# STorM32_Micro_Logger_v132_micro.net
KiCad netlist of a schematic drawn in EAGLE
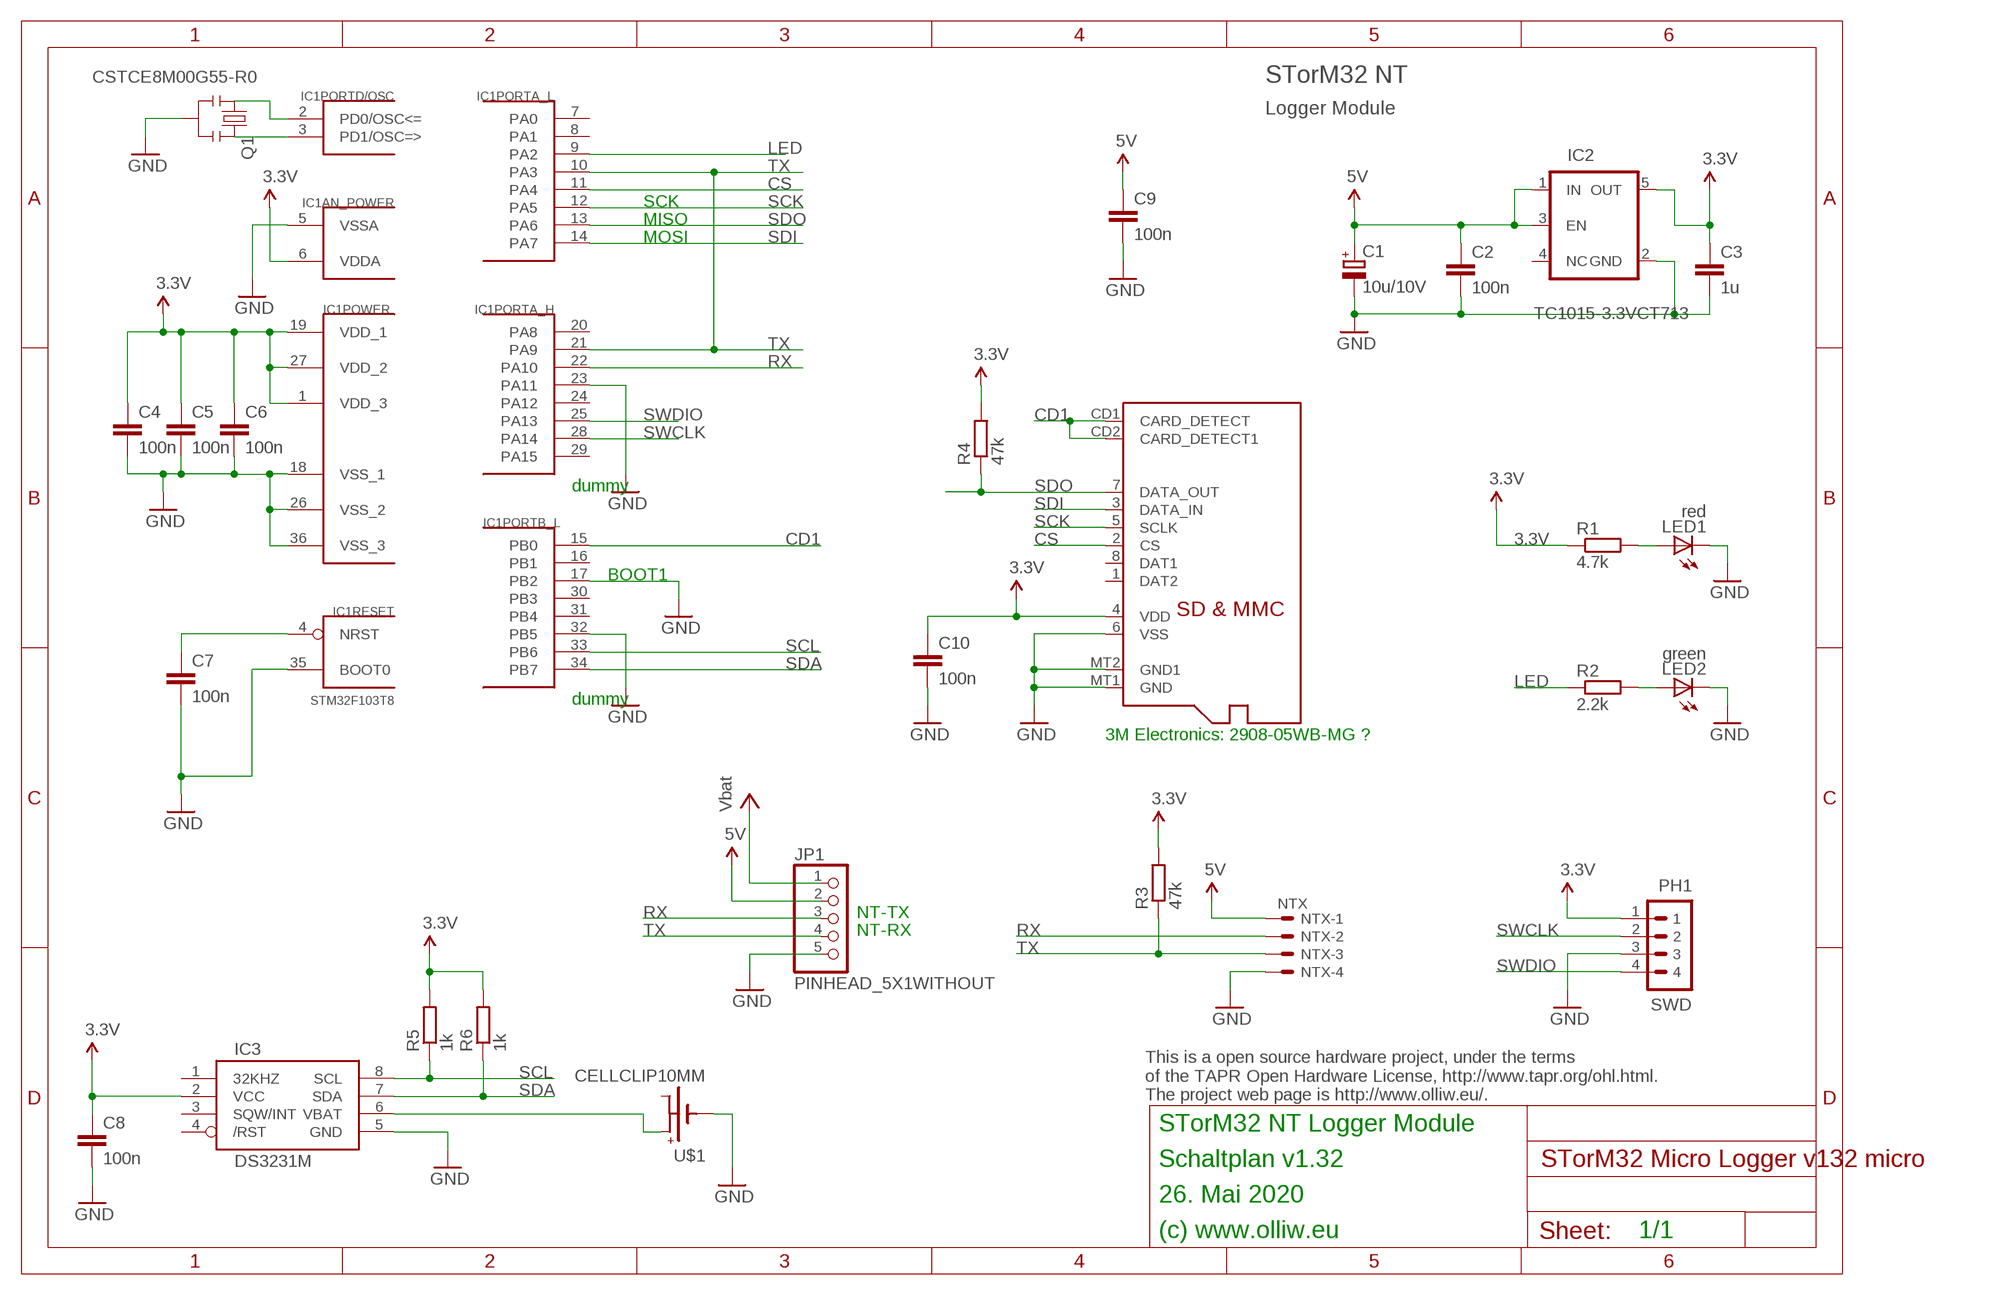
[diagram p0: schematic, sheet 1]

(export (version "E")
  (design (tool "Eeschema 10.0.6"))
  (components
    (comp (ref "C1")
      (value "10u/10V")
      (footprint "eagle-import:SMC_B")
      (libsource (lib "eagle-import") (part "CPOL-EUSMCB"))
    )
    (comp (ref "C2")
      (value "100n")
      (footprint "eagle-import:C0603")
      (libsource (lib "eagle-import") (part "C-EUC0603"))
    )
    (comp (ref "C3")
      (value "1u")
      (footprint "eagle-import:C0603")
      (libsource (lib "eagle-import") (part "C-EUC0603"))
    )
    (comp (ref "C4")
      (value "100n")
      (footprint "eagle-import:C0402")
      (libsource (lib "eagle-import") (part "C-EUC0402"))
    )
    (comp (ref "C5")
      (value "100n")
      (footprint "eagle-import:C0402")
      (libsource (lib "eagle-import") (part "C-EUC0402"))
    )
    (comp (ref "C6")
      (value "100n")
      (footprint "eagle-import:C0402")
      (libsource (lib "eagle-import") (part "C-EUC0402"))
    )
    (comp (ref "C7")
      (value "100n")
      (footprint "eagle-import:C0402")
      (libsource (lib "eagle-import") (part "C-EUC0402"))
    )
    (comp (ref "C8")
      (value "100n")
      (footprint "eagle-import:C0402")
      (libsource (lib "eagle-import") (part "C-EUC0402"))
    )
    (comp (ref "C9")
      (value "100n")
      (footprint "eagle-import:C0603")
      (libsource (lib "eagle-import") (part "C-EUC0603"))
    )
    (comp (ref "C10")
      (value "100n")
      (footprint "eagle-import:C0402")
      (libsource (lib "eagle-import") (part "C-EUC0402"))
    )
    (comp (ref "IC1")
      (value "STM32F103T8")
      (footprint "eagle-import:VFQFPN36")
      (libsource (lib "eagle-import") (part "STM32F10XTXU6"))
    )
    (comp (ref "IC2")
      (value "TC1015-3.3VCT713")
      (footprint "eagle-import:SOT23-5")
      (libsource (lib "eagle-import") (part "V_REG_TPS76433SOT23-5"))
    )
    (comp (ref "IC3")
      (value "DS3231M")
      (footprint "eagle-import:SO08")
      (libsource (lib "eagle-import") (part "DS3231M"))
    )
    (comp (ref "JP1")
      (value "PINHEAD_5X1WITHOUT")
      (footprint "eagle-import:PINHEAD_5X1_WO")
      (libsource (lib "eagle-import") (part "PINHEAD_5X1WITHOUT"))
    )
    (comp (ref "LED1")
      (value "red")
      (footprint "eagle-import:CHIPLED_0603")
      (libsource (lib "eagle-import") (part "LEDCHIPLED_0603"))
    )
    (comp (ref "LED2")
      (value "green")
      (footprint "eagle-import:CHIPLED_0603")
      (libsource (lib "eagle-import") (part "LEDCHIPLED_0603"))
    )
    (comp (ref "NTX")
      (value "NTX")
      (footprint "eagle-import:SM04B-SRSS-TB")
      (libsource (lib "eagle-import") (part "?M04B-SRSS-TBS"))
    )
    (comp (ref "PH1")
      (value "SWD")
      (footprint "eagle-import:4X1_1P27_OCT_BILEX")
      (libsource (lib "eagle-import") (part "P4X1_1P27-OCT_BILEX"))
    )
    (comp (ref "Q1")
      (value "CSTCE8M00G55-R0")
      (footprint "eagle-import:RESONATOR-SMD")
      (libsource (lib "eagle-import") (part "RESONATORSMD"))
    )
    (comp (ref "R1")
      (value "4.7k")
      (footprint "eagle-import:R0402")
      (libsource (lib "eagle-import") (part "R-EU_R0402"))
    )
    (comp (ref "R2")
      (value "2.2k")
      (footprint "eagle-import:R0402")
      (libsource (lib "eagle-import") (part "R-EU_R0402"))
    )
    (comp (ref "R3")
      (value "47k")
      (footprint "eagle-import:R0402")
      (libsource (lib "eagle-import") (part "R-EU_R0402"))
    )
    (comp (ref "R4")
      (value "47k")
      (footprint "eagle-import:R0402")
      (libsource (lib "eagle-import") (part "R-EU_R0402"))
    )
    (comp (ref "R5")
      (value "1k")
      (footprint "eagle-import:R0402")
      (libsource (lib "eagle-import") (part "R-EU_R0402"))
    )
    (comp (ref "R6")
      (value "1k")
      (footprint "eagle-import:R0402")
      (libsource (lib "eagle-import") (part "R-EU_R0402"))
    )
    (comp (ref "U$1")
      (value "CELLCLIP10MM")
      (footprint "eagle-import:CELLCLIP-10MM")
      (libsource (lib "eagle-import") (part "CELLCLIP10MM"))
    )
    (comp (ref "U1")
      (value "3M 2908-05WB-MG ??")
      (footprint "eagle-import:MICROSD")
      (libsource (lib "eagle-import") (part "MICROSD"))
    )
  )
  (nets
    (net (code "1") (name "/CD1") (class "Default")
      (node (ref "IC1") (pin "15") (pinfunction "PB0_15") (pintype "bidirectional"))
      (node (ref "U1") (pin "CD1") (pinfunction "CARD_DETECT_CD1") (pintype "passive"))
      (node (ref "U1") (pin "CD2") (pinfunction "CARD_DETECT1_CD2") (pintype "passive"))
    )
    (net (code "2") (name "/CS") (class "Default")
      (node (ref "IC1") (pin "11") (pinfunction "PA4_11") (pintype "bidirectional"))
      (node (ref "U1") (pin "2") (pinfunction "CS_2") (pintype "input"))
    )
    (net (code "3") (name "/LED") (class "Default")
      (node (ref "IC1") (pin "9") (pinfunction "PA2_9") (pintype "bidirectional"))
      (node (ref "R2") (pin "1") (pinfunction "1_1") (pintype "passive"))
    )
    (net (code "4") (name "/RX") (class "Default")
      (node (ref "IC1") (pin "22") (pinfunction "PA10_22") (pintype "bidirectional"))
      (node (ref "JP1") (pin "3") (pinfunction "3_3") (pintype "passive"))
      (node (ref "NTX") (pin "2") (pinfunction "S_2") (pintype "passive"))
    )
    (net (code "5") (name "/SCK") (class "Default")
      (node (ref "IC1") (pin "12") (pinfunction "PA5_12") (pintype "bidirectional"))
      (node (ref "U1") (pin "5") (pinfunction "SCLK_5") (pintype "input"))
    )
    (net (code "6") (name "/SCL") (class "Default")
      (node (ref "IC1") (pin "33") (pinfunction "PB6_33") (pintype "bidirectional"))
      (node (ref "IC3") (pin "8") (pinfunction "SCL_8") (pintype "bidirectional"))
      (node (ref "R5") (pin "1") (pinfunction "1_1") (pintype "passive"))
    )
    (net (code "7") (name "/SDA") (class "Default")
      (node (ref "IC1") (pin "34") (pinfunction "PB7_34") (pintype "bidirectional"))
      (node (ref "IC3") (pin "7") (pinfunction "SDA_7") (pintype "bidirectional"))
      (node (ref "R6") (pin "1") (pinfunction "1_1") (pintype "passive"))
    )
    (net (code "8") (name "/SDI") (class "Default")
      (node (ref "IC1") (pin "14") (pinfunction "PA7_14") (pintype "bidirectional"))
      (node (ref "U1") (pin "3") (pinfunction "DATA_IN_3") (pintype "input"))
    )
    (net (code "9") (name "/SDO") (class "Default")
      (node (ref "IC1") (pin "13") (pinfunction "PA6_13") (pintype "bidirectional"))
      (node (ref "R4") (pin "1") (pinfunction "1_1") (pintype "passive"))
      (node (ref "U1") (pin "7") (pinfunction "DATA_OUT_7") (pintype "output"))
    )
    (net (code "10") (name "/SWCLK") (class "Default")
      (node (ref "IC1") (pin "28") (pinfunction "PA14_28") (pintype "bidirectional"))
      (node (ref "PH1") (pin "2") (pinfunction "2_2") (pintype "passive"))
    )
    (net (code "11") (name "/SWDIO") (class "Default")
      (node (ref "IC1") (pin "25") (pinfunction "PA13_25") (pintype "bidirectional"))
      (node (ref "PH1") (pin "4") (pinfunction "4_4") (pintype "passive"))
    )
    (net (code "12") (name "/TX") (class "Default")
      (node (ref "IC1") (pin "10") (pinfunction "PA3_10") (pintype "bidirectional"))
      (node (ref "IC1") (pin "21") (pinfunction "PA9_21") (pintype "bidirectional"))
      (node (ref "JP1") (pin "4") (pinfunction "4_4") (pintype "passive"))
      (node (ref "NTX") (pin "3") (pinfunction "S_3") (pintype "passive"))
      (node (ref "R3") (pin "1") (pinfunction "1_1") (pintype "passive"))
    )
    (net (code "13") (name "3.3V") (class "Default")
      (node (ref "C10") (pin "1") (pinfunction "1_1") (pintype "passive"))
      (node (ref "C3") (pin "1") (pinfunction "1_1") (pintype "passive"))
      (node (ref "C4") (pin "1") (pinfunction "1_1") (pintype "passive"))
      (node (ref "C5") (pin "1") (pinfunction "1_1") (pintype "passive"))
      (node (ref "C6") (pin "1") (pinfunction "1_1") (pintype "passive"))
      (node (ref "C8") (pin "1") (pinfunction "1_1") (pintype "passive"))
      (node (ref "IC1") (pin "1") (pinfunction "VDD_3_1") (pintype "power_in"))
      (node (ref "IC1") (pin "19") (pinfunction "VDD_1_19") (pintype "power_in"))
      (node (ref "IC1") (pin "27") (pinfunction "VDD_2_27") (pintype "power_in"))
      (node (ref "IC1") (pin "6") (pinfunction "VDDA_6") (pintype "power_in"))
      (node (ref "IC2") (pin "5") (pinfunction "OUT_5") (pintype "output"))
      (node (ref "IC3") (pin "2") (pinfunction "VCC_2") (pintype "power_in"))
      (node (ref "PH1") (pin "1") (pinfunction "1_1") (pintype "passive"))
      (node (ref "R1") (pin "1") (pinfunction "1_1") (pintype "passive"))
      (node (ref "R3") (pin "2") (pinfunction "2_2") (pintype "passive"))
      (node (ref "R4") (pin "2") (pinfunction "2_2") (pintype "passive"))
      (node (ref "R5") (pin "2") (pinfunction "2_2") (pintype "passive"))
      (node (ref "R6") (pin "2") (pinfunction "2_2") (pintype "passive"))
      (node (ref "U1") (pin "4") (pinfunction "VDD_4") (pintype "power_in"))
    )
    (net (code "14") (name "5V") (class "Default")
      (node (ref "C1") (pin "+") (pinfunction "+_+") (pintype "passive"))
      (node (ref "C2") (pin "1") (pinfunction "1_1") (pintype "passive"))
      (node (ref "C9") (pin "1") (pinfunction "1_1") (pintype "passive"))
      (node (ref "IC2") (pin "1") (pinfunction "IN_1") (pintype "power_in"))
      (node (ref "IC2") (pin "3") (pinfunction "EN_3") (pintype "input"))
      (node (ref "JP1") (pin "2") (pinfunction "2_2") (pintype "passive"))
      (node (ref "NTX") (pin "1") (pinfunction "S_1") (pintype "passive"))
    )
    (net (code "15") (name "GND") (class "Default")
      (node (ref "C1") (pin "-") (pinfunction "-_-") (pintype "passive"))
      (node (ref "C10") (pin "2") (pinfunction "2_2") (pintype "passive"))
      (node (ref "C2") (pin "2") (pinfunction "2_2") (pintype "passive"))
      (node (ref "C3") (pin "2") (pinfunction "2_2") (pintype "passive"))
      (node (ref "C4") (pin "2") (pinfunction "2_2") (pintype "passive"))
      (node (ref "C5") (pin "2") (pinfunction "2_2") (pintype "passive"))
      (node (ref "C6") (pin "2") (pinfunction "2_2") (pintype "passive"))
      (node (ref "C7") (pin "2") (pinfunction "2_2") (pintype "passive"))
      (node (ref "C8") (pin "2") (pinfunction "2_2") (pintype "passive"))
      (node (ref "C9") (pin "2") (pinfunction "2_2") (pintype "passive"))
      (node (ref "IC1") (pin "17") (pinfunction "PB2_17") (pintype "bidirectional"))
      (node (ref "IC1") (pin "18") (pinfunction "VSS_1_18") (pintype "power_in"))
      (node (ref "IC1") (pin "23") (pinfunction "PA11_23") (pintype "bidirectional"))
      (node (ref "IC1") (pin "26") (pinfunction "VSS_2_26") (pintype "power_in"))
      (node (ref "IC1") (pin "32") (pinfunction "PB5_32") (pintype "bidirectional"))
      (node (ref "IC1") (pin "35") (pinfunction "BOOT0_35") (pintype "input"))
      (node (ref "IC1") (pin "36") (pinfunction "VSS_3_36") (pintype "power_in"))
      (node (ref "IC1") (pin "5") (pinfunction "VSSA_5") (pintype "power_in"))
      (node (ref "IC2") (pin "2") (pinfunction "GND_2") (pintype "power_in"))
      (node (ref "IC3") (pin "5") (pinfunction "GND_5") (pintype "power_in"))
      (node (ref "JP1") (pin "5") (pinfunction "5_5") (pintype "passive"))
      (node (ref "LED1") (pin "C") (pinfunction "C_C") (pintype "passive"))
      (node (ref "LED2") (pin "C") (pinfunction "C_C") (pintype "passive"))
      (node (ref "NTX") (pin "4") (pinfunction "S_4") (pintype "passive"))
      (node (ref "PH1") (pin "3") (pinfunction "3_3") (pintype "passive"))
      (node (ref "Q1") (pin "2") (pinfunction "2_2") (pintype "passive"))
      (node (ref "U$1") (pin "P$1") (pinfunction "GND_P$1") (pintype "power_in"))
      (node (ref "U1") (pin "6") (pinfunction "VSS_6") (pintype "power_in"))
      (node (ref "U1") (pin "MT1") (pinfunction "GND_MT1") (pintype "power_in"))
      (node (ref "U1") (pin "MT2") (pinfunction "GND1_MT2") (pintype "power_in"))
    )
    (net (code "16") (name "Net-(IC1E-PD0{slash}OSC<=)") (class "Default")
      (node (ref "IC1") (pin "2") (pinfunction "PD0/OSC<=_2") (pintype "bidirectional"))
      (node (ref "Q1") (pin "1") (pinfunction "1_1") (pintype "passive"))
    )
    (net (code "17") (name "Net-(IC1E-PD1{slash}OSC=>)") (class "Default")
      (node (ref "IC1") (pin "3") (pinfunction "PD1/OSC=>_3") (pintype "bidirectional"))
      (node (ref "Q1") (pin "3") (pinfunction "3_3") (pintype "passive"))
    )
    (net (code "18") (name "Net-(IC1G-NRST)") (class "Default")
      (node (ref "C7") (pin "1") (pinfunction "1_1") (pintype "passive"))
      (node (ref "IC1") (pin "4") (pinfunction "NRST_4") (pintype "input"))
    )
    (net (code "19") (name "Net-(IC3-VBAT)") (class "Default")
      (node (ref "IC3") (pin "6") (pinfunction "VBAT_6") (pintype "power_in"))
      (node (ref "U$1") (pin "P$2") (pinfunction "BAT+_P$2") (pintype "power_in"))
    )
    (net (code "20") (name "Net-(LED1-PadA)") (class "Default")
      (node (ref "LED1") (pin "A") (pinfunction "A_A") (pintype "passive"))
      (node (ref "R1") (pin "2") (pinfunction "2_2") (pintype "passive"))
    )
    (net (code "21") (name "Net-(LED2-PadA)") (class "Default")
      (node (ref "LED2") (pin "A") (pinfunction "A_A") (pintype "passive"))
      (node (ref "R2") (pin "2") (pinfunction "2_2") (pintype "passive"))
    )
    (net (code "22") (name "Vbat") (class "Default")
      (node (ref "JP1") (pin "1") (pinfunction "1_1") (pintype "passive"))
    )
    (net (code "23") (name "unconnected-(IC1B-PA8-Pad20)") (class "Default")
      (node (ref "IC1") (pin "20") (pinfunction "PA8_20") (pintype "bidirectional"))
    )
    (net (code "24") (name "unconnected-(IC1B-PA12-Pad24)") (class "Default")
      (node (ref "IC1") (pin "24") (pinfunction "PA12_24") (pintype "bidirectional"))
    )
    (net (code "25") (name "unconnected-(IC1B-PA15-Pad29)") (class "Default")
      (node (ref "IC1") (pin "29") (pinfunction "PA15_29") (pintype "bidirectional"))
    )
    (net (code "26") (name "unconnected-(IC1C-PA0-Pad7)") (class "Default")
      (node (ref "IC1") (pin "7") (pinfunction "PA0_7") (pintype "bidirectional"))
    )
    (net (code "27") (name "unconnected-(IC1C-PA1-Pad8)") (class "Default")
      (node (ref "IC1") (pin "8") (pinfunction "PA1_8") (pintype "bidirectional"))
    )
    (net (code "28") (name "unconnected-(IC1D-PB1-Pad16)") (class "Default")
      (node (ref "IC1") (pin "16") (pinfunction "PB1_16") (pintype "bidirectional"))
    )
    (net (code "29") (name "unconnected-(IC1D-PB3-Pad30)") (class "Default")
      (node (ref "IC1") (pin "30") (pinfunction "PB3_30") (pintype "bidirectional"))
    )
    (net (code "30") (name "unconnected-(IC1D-PB4-Pad31)") (class "Default")
      (node (ref "IC1") (pin "31") (pinfunction "PB4_31") (pintype "bidirectional"))
    )
    (net (code "31") (name "unconnected-(IC2-NC-Pad4)") (class "Default")
      (node (ref "IC2") (pin "4") (pinfunction "NC_4") (pintype "passive"))
    )
    (net (code "32") (name "unconnected-(IC3-32KHZ-Pad1)") (class "Default")
      (node (ref "IC3") (pin "1") (pinfunction "32KHZ_1") (pintype "open_collector"))
    )
    (net (code "33") (name "unconnected-(IC3-SQW{slash}INT-Pad3)") (class "Default")
      (node (ref "IC3") (pin "3") (pinfunction "SQW/INT_3") (pintype "open_collector"))
    )
    (net (code "34") (name "unconnected-(IC3-{slash}RST-Pad4)") (class "Default")
      (node (ref "IC3") (pin "4") (pinfunction "/RST_4") (pintype "bidirectional"))
    )
    (net (code "35") (name "unconnected-(U1-DAT1-Pad8)") (class "Default")
      (node (ref "U1") (pin "8") (pinfunction "DAT1_8") (pintype "bidirectional"))
    )
    (net (code "36") (name "unconnected-(U1-DAT2-Pad1)") (class "Default")
      (node (ref "U1") (pin "1") (pinfunction "DAT2_1") (pintype "bidirectional"))
    )
  )
)
